# Avionics.net
KiCad netlist of a schematic drawn in Altium Designer
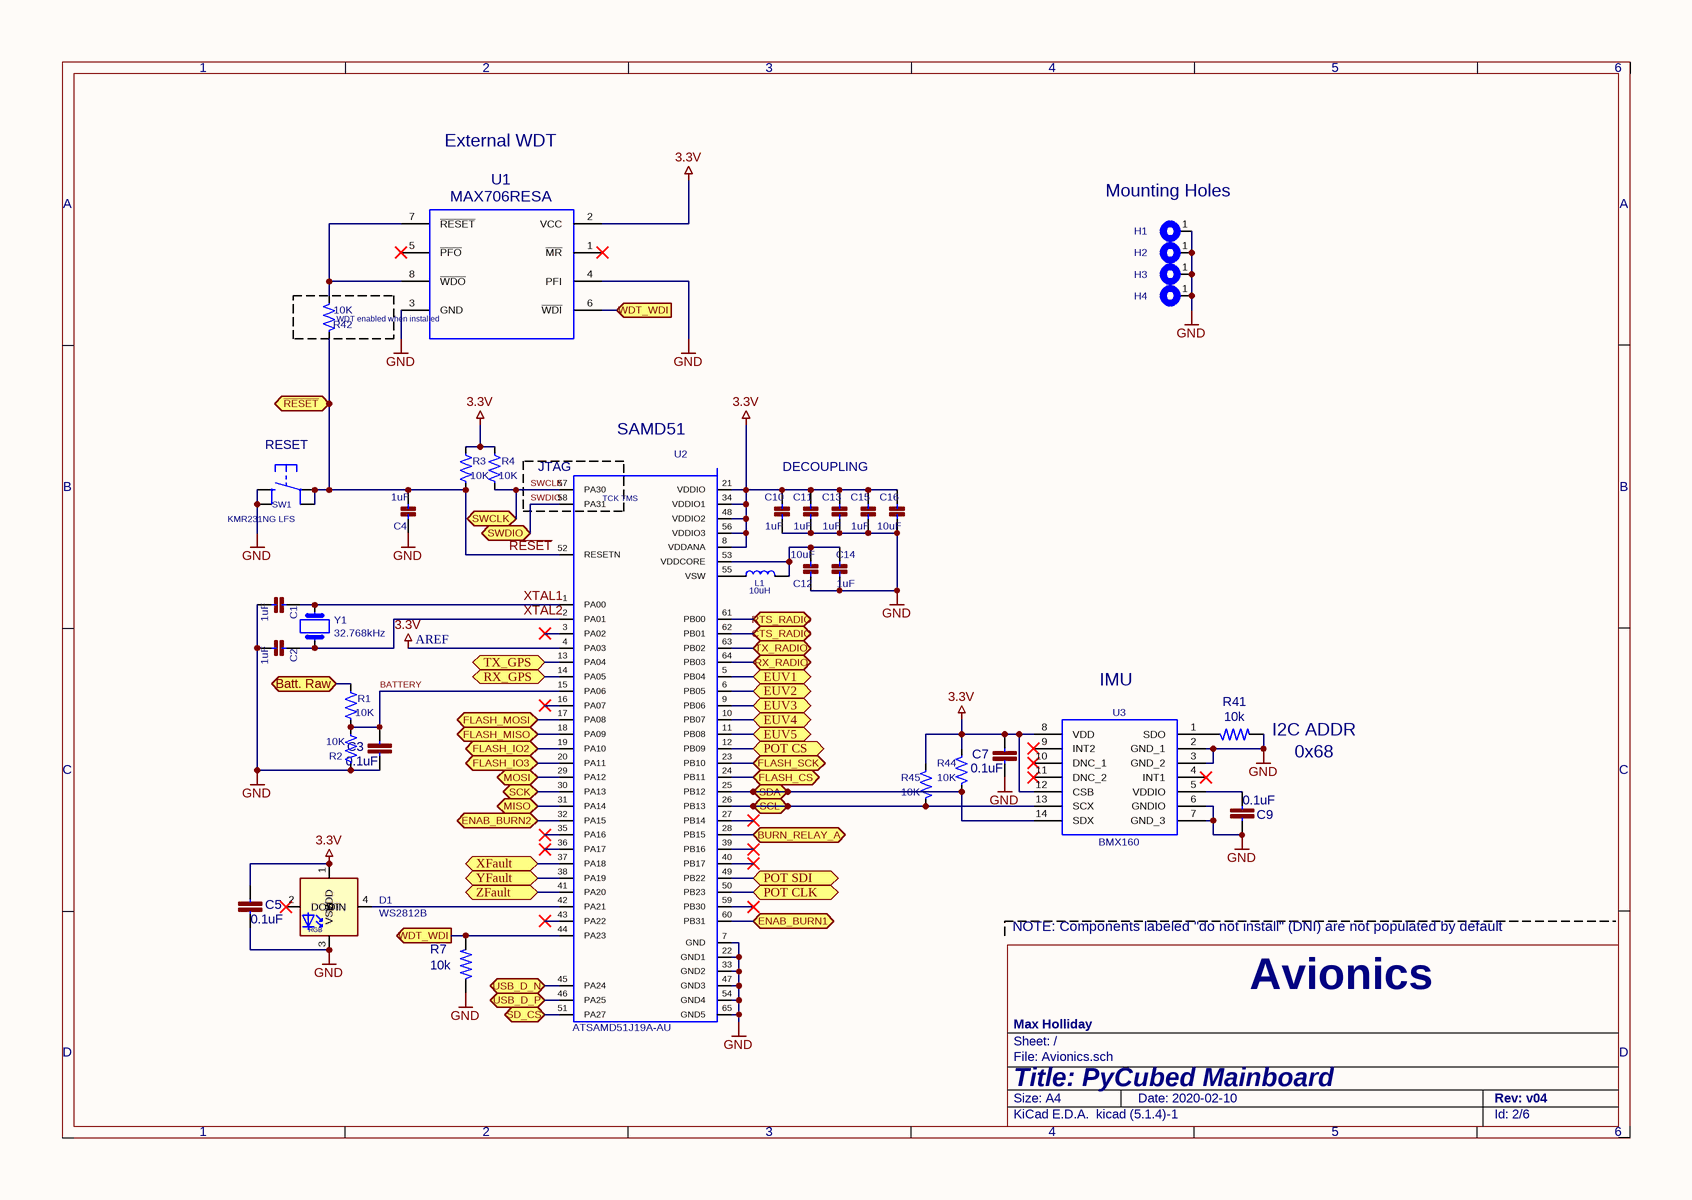
[diagram p0: Avionics.SchDoc]

(export (version "E")
  (design (tool "Eeschema 10.0.6"))
  (components
    (comp (ref "C1")
      (value "1uF")
      (footprint "C_0603_1608Metric")
      (fields (field (name "MPN") "CL10A105KB8NNNC"))
      (libsource (lib "mainboard_1") (part "CAP_CERAMIC0603_NO-Adafruit_Feather_M4_Express-eagle-import-lab64_SAM32-rescue-SAMD-10-rescue-SAM32-rescue"))
    )
    (comp (ref "C2")
      (value "1uF")
      (footprint "C_0603_1608Metric")
      (fields (field (name "MPN") "CL10A105KB8NNNC"))
      (libsource (lib "mainboard_1") (part "CAP_CERAMIC0603_NO-Adafruit_Feather_M4_Express-eagle-import-lab64_SAM32-rescue-SAMD-10-rescue-SAM32-rescue"))
    )
    (comp (ref "C3")
      (value "0.1uF")
      (footprint "C_0603_1608Metric")
      (fields (field (name "MPN") "CL10B104KB8NNNL"))
      (libsource (lib "") (part "0.1UF-25V(+80_-20%)(0603)_2"))
    )
    (comp (ref "C4")
      (value "1uF")
      (footprint "C_0603_1608Metric")
      (fields (field (name "MPN") "CL10A105KB8NNNC"))
      (libsource (lib "") (part "CAP_CERAMIC0603_NO-Adafruit_Feather_M4_Express-eagle-import-lab64_SAM32-rescue-SAMD-10-rescue-SAM32-rescue_1"))
    )
    (comp (ref "C5")
      (value "0.1uF")
      (footprint "C_0603_1608Metric")
      (fields (field (name "MPN") "CL10B104KB8NNNL"))
      (libsource (lib "mainboard_1") (part "0.1UF-25V(+80_-20%)(0603)"))
    )
    (comp (ref "C7")
      (value "0.1uF")
      (footprint "C_0603_1608Metric")
      (fields (field (name "MPN") "CL10B104KB8NNNL"))
      (libsource (lib "") (part "0.1UF-25V(+80_-20%)(0603)_2"))
    )
    (comp (ref "C9")
      (value "0.1uF")
      (footprint "C_0603_1608Metric")
      (fields (field (name "MPN") "CL10B104KB8NNNL"))
      (libsource (lib "") (part "0.1UF-25V(+80_-20%)(0603)_1"))
    )
    (comp (ref "C10")
      (value "1uF")
      (footprint "C_0603_1608Metric")
      (fields (field (name "MPN") "CL10A105KB8NNNC"))
      (libsource (lib "mainboard_1") (part "CAP_CERAMIC0603_NO-Adafruit_Feather_M4_Express-eagle-import-lab64_SAM32-rescue-SAMD-10-rescue-SAM32-rescue"))
    )
    (comp (ref "C11")
      (value "1uF")
      (footprint "C_0603_1608Metric")
      (fields (field (name "MPN") "CL10A105KB8NNNC"))
      (libsource (lib "mainboard_1") (part "CAP_CERAMIC0603_NO-Adafruit_Feather_M4_Express-eagle-import-lab64_SAM32-rescue-SAMD-10-rescue-SAM32-rescue"))
    )
    (comp (ref "C12")
      (value "10uF")
      (footprint "C_0603_1608Metric")
      (fields (field (name "MPN") "CL10A106MP8NNNC"))
      (libsource (lib "") (part "CAP_CERAMIC0805-NOOUTLINE-Adafruit_Feather_M4_Express-eagle-import-lab64_SAM32-rescue-SAMD-10-rescue-SAM32-rescue_1"))
    )
    (comp (ref "C13")
      (value "1uF")
      (footprint "C_0603_1608Metric")
      (fields (field (name "MPN") "CL10A105KB8NNNC"))
      (libsource (lib "mainboard_1") (part "CAP_CERAMIC0603_NO-Adafruit_Feather_M4_Express-eagle-import-lab64_SAM32-rescue-SAMD-10-rescue-SAM32-rescue"))
    )
    (comp (ref "C14")
      (value "1uF")
      (footprint "C_0603_1608Metric")
      (fields (field (name "MPN") "CL10A105KB8NNNC"))
      (libsource (lib "") (part "CAP_CERAMIC0603_NO-Adafruit_Feather_M4_Express-eagle-import-lab64_SAM32-rescue-SAMD-10-rescue-SAM32-rescue_2"))
    )
    (comp (ref "C15")
      (value "1uF")
      (footprint "C_0603_1608Metric")
      (fields (field (name "MPN") "CL10A105KB8NNNC"))
      (libsource (lib "mainboard_1") (part "CAP_CERAMIC0603_NO-Adafruit_Feather_M4_Express-eagle-import-lab64_SAM32-rescue-SAMD-10-rescue-SAM32-rescue"))
    )
    (comp (ref "C16")
      (value "10uF")
      (footprint "C_0603_1608Metric")
      (fields (field (name "MPN") "CL10A106MP8NNNC"))
      (libsource (lib "mainboard_1") (part "CAP_CERAMIC0805-NOOUTLINE-Adafruit_Feather_M4_Express-eagle-import-lab64_SAM32-rescue-SAMD-10-rescue-SAM32-rescue"))
    )
    (comp (ref "D1")
      (value "WS2812B")
      (footprint "LED_WS2812B_PLCC4_5.0x5.0mm_P3.2mm")
      (fields (field (name "MPN") "COM-16347"))
      (libsource (lib "mainboard_1") (part "WS2812B"))
    )
    (comp (ref "H1")
      (value "MountingHole_Pad")
      (footprint "MountingHole_3.2mm_M3_DIN965_Pad")
      (libsource (lib "mainboard_1") (part "MountingHole_Pad"))
    )
    (comp (ref "H2")
      (value "MountingHole_Pad")
      (footprint "MountingHole_3.2mm_M3_DIN965_Pad")
      (libsource (lib "mainboard_1") (part "MountingHole_Pad"))
    )
    (comp (ref "H3")
      (value "MountingHole_Pad")
      (footprint "MountingHole_3.2mm_M3_DIN965_Pad")
      (libsource (lib "mainboard_1") (part "MountingHole_Pad"))
    )
    (comp (ref "H4")
      (value "MountingHole_Pad")
      (footprint "MountingHole_3.2mm_M3_DIN965_Pad")
      (libsource (lib "mainboard_1") (part "MountingHole_Pad"))
    )
    (comp (ref "L1")
      (value "10uH")
      (footprint "L_0805_2012Metric_Pad1.15x1.40mm_HandSolder")
      (fields (field (name "MPN") "LBR2012T100K"))
      (libsource (lib "mainboard_1") (part "INDUCTOR-Adafruit_Feather_M4_Express-eagle-import-lab64_SAM32-rescue-SAMD-10-rescue-SAM32-rescue"))
    )
    (comp (ref "R1")
      (value "10K")
      (footprint "R_0603_1608Metric")
      (fields (field (name "MPN") "CRGCQ0603J10K"))
      (libsource (lib "mainboard_1") (part "R_US"))
    )
    (comp (ref "R2")
      (value "10K")
      (footprint "R_0603_1608Metric")
      (fields (field (name "MPN") "CRGCQ0603J10K"))
      (libsource (lib "mainboard_1") (part "R_US"))
    )
    (comp (ref "R3")
      (value "10K")
      (footprint "R_0603_1608Metric")
      (fields (field (name "MPN") "CRGCQ0603J10K"))
      (libsource (lib "mainboard_1") (part "R_US"))
    )
    (comp (ref "R4")
      (value "10K")
      (footprint "R_0603_1608Metric")
      (fields (field (name "MPN") "CRGCQ0603J10K"))
      (libsource (lib "mainboard_1") (part "R_US"))
    )
    (comp (ref "R7")
      (value "10k")
      (footprint "R_0603_1608Metric")
      (fields (field (name "MPN") "RNCP0603FTD10K0"))
      (libsource (lib "mainboard_1") (part "R-US_R0603"))
    )
    (comp (ref "R41")
      (value "10k")
      (footprint "R_0603_1608Metric")
      (fields (field (name "MPN") "RNCP0603FTD10K0"))
      (libsource (lib "mainboard_1") (part "R-US_R0603"))
    )
    (comp (ref "R42")
      (value "10K")
      (footprint "R_0603_1608Metric")
      (fields (field (name "MPN") "CRGCQ0603J10K"))
      (libsource (lib "mainboard_1") (part "R_US"))
    )
    (comp (ref "R44")
      (value "10K")
      (footprint "R_0603_1608Metric")
      (fields (field (name "MPN") "CRGCQ0603J10K"))
      (libsource (lib "mainboard_1") (part "R_US"))
    )
    (comp (ref "R45")
      (value "10K")
      (footprint "R_0603_1608Metric")
      (fields (field (name "MPN") "CRGCQ0603J10K"))
      (libsource (lib "mainboard_1") (part "R_US"))
    )
    (comp (ref "SW1")
      (value "KMR231NG LFS")
      (footprint "BTN_KMR2_4.6X2.8")
      (libsource (lib "mainboard_1") (part "SWITCH_TACT_SMT4.6X2.8-Adafruit_Feather_M4_Express-eagle-import-lab64_SAM32-rescue-SAMD-10-rescue-SAM32-rescue"))
    )
    (comp (ref "U1")
      (value "MAX706RESA")
      (footprint "SO-8_3.9x4.9mm_P1.27mm")
      (libsource (lib "mainboard_1") (part "MAX708RESA-T"))
    )
    (comp (ref "U2")
      (value "120MHZ 512KB Flash 64 TQFP")
      (footprint "ATSAMD51J19A-MU")
      (fields (field (name "PROTO") "ATSAMD51J19A-AU") (field (name "MPN") "ATSAMD51J19A-AU"))
      (libsource (lib "mainboard_1") (part "ATSAMD51J20A-AU-ATSAMD51J20A-AU-lab64_SAM32-rescue-lab64_SAM32-rescue-SAMD-10-rescue-SAM32-rescue"))
    )
    (comp (ref "U3") (value "BMX160") (footprint "BMX160") (libsource (lib "mainboard_1") (part "BMX160")))
    (comp (ref "Y1")
      (value "32.768kHz")
      (footprint "Crystal_SMD_3215-2Pin_3.2x1.5mm")
      (fields (field (name "MPN") "ABS07-32.768KHZ-T"))
      (libsource (lib "mainboard_1") (part "Crystal"))
    )
  )
  (nets
    (net (code "1") (name "/BATTERY") (class "Default")
      (node (ref "C3") (pin "1") (pinfunction "1_1") (pintype "passive"))
      (node (ref "R1") (pin "2") (pinfunction "2_2") (pintype "passive"))
      (node (ref "R2") (pin "2") (pinfunction "2_2") (pintype "passive"))
      (node (ref "U2") (pin "15") (pinfunction "PA06_15") (pintype "passive"))
    )
    (net (code "2") (name "/BURN_RELAY_A") (class "Default")
      (node (ref "U2") (pin "28") (pinfunction "PB15_28") (pintype "passive"))
    )
    (net (code "3") (name "/Batt. Raw") (class "Default")
      (node (ref "R1") (pin "1") (pinfunction "1_1") (pintype "passive"))
    )
    (net (code "4") (name "/CTS_RADIO") (class "Default")
      (node (ref "U2") (pin "62") (pinfunction "PB01_62") (pintype "passive"))
    )
    (net (code "5") (name "/ENAB_BURN1") (class "Default")
      (node (ref "U2") (pin "60") (pinfunction "PB31_60") (pintype "passive"))
    )
    (net (code "6") (name "/ENAB_BURN2") (class "Default")
      (node (ref "U2") (pin "32") (pinfunction "PA15_32") (pintype "passive"))
    )
    (net (code "7") (name "/EUV1") (class "Default")
      (node (ref "U2") (pin "5") (pinfunction "PB04_5") (pintype "passive"))
    )
    (net (code "8") (name "/EUV2") (class "Default")
      (node (ref "U2") (pin "6") (pinfunction "PB05_6") (pintype "passive"))
    )
    (net (code "9") (name "/EUV3") (class "Default")
      (node (ref "U2") (pin "9") (pinfunction "PB06_9") (pintype "passive"))
    )
    (net (code "10") (name "/EUV4") (class "Default")
      (node (ref "U2") (pin "10") (pinfunction "PB07_10") (pintype "passive"))
    )
    (net (code "11") (name "/EUV5") (class "Default")
      (node (ref "U2") (pin "11") (pinfunction "PB08_11") (pintype "passive"))
    )
    (net (code "12") (name "/FLASH_CS") (class "Default")
      (node (ref "U2") (pin "24") (pinfunction "PB11_24") (pintype "passive"))
    )
    (net (code "13") (name "/FLASH_IO2") (class "Default")
      (node (ref "U2") (pin "19") (pinfunction "PA10_19") (pintype "passive"))
    )
    (net (code "14") (name "/FLASH_IO3") (class "Default")
      (node (ref "U2") (pin "20") (pinfunction "PA11_20") (pintype "passive"))
    )
    (net (code "15") (name "/FLASH_MISO") (class "Default")
      (node (ref "U2") (pin "18") (pinfunction "PA09_18") (pintype "passive"))
    )
    (net (code "16") (name "/FLASH_MOSI") (class "Default")
      (node (ref "U2") (pin "17") (pinfunction "PA08_17") (pintype "passive"))
    )
    (net (code "17") (name "/FLASH_SCK") (class "Default")
      (node (ref "U2") (pin "23") (pinfunction "PB10_23") (pintype "passive"))
    )
    (net (code "18") (name "/MISO") (class "Default")
      (node (ref "U2") (pin "31") (pinfunction "PA14_31") (pintype "passive"))
    )
    (net (code "19") (name "/MOSI") (class "Default")
      (node (ref "U2") (pin "29") (pinfunction "PA12_29") (pintype "passive"))
    )
    (net (code "20") (name "/POT CLK") (class "Default")
      (node (ref "U2") (pin "50") (pinfunction "PB23_50") (pintype "passive"))
    )
    (net (code "21") (name "/POT CS") (class "Default")
      (node (ref "U2") (pin "12") (pinfunction "PB09_12") (pintype "passive"))
    )
    (net (code "22") (name "/POT SDI") (class "Default")
      (node (ref "U2") (pin "49") (pinfunction "PB22_49") (pintype "passive"))
    )
    (net (code "23") (name "/RTS_RADIO") (class "Default")
      (node (ref "U2") (pin "61") (pinfunction "PB00_61") (pintype "passive"))
    )
    (net (code "24") (name "/RX_GPS") (class "Default")
      (node (ref "U2") (pin "14") (pinfunction "PA05_14") (pintype "passive"))
    )
    (net (code "25") (name "/RX_RADIO") (class "Default")
      (node (ref "U2") (pin "64") (pinfunction "PB03_64") (pintype "passive"))
    )
    (net (code "26") (name "/SCK") (class "Default")
      (node (ref "U2") (pin "30") (pinfunction "PA13_30") (pintype "passive"))
    )
    (net (code "27") (name "/SCL") (class "Default")
      (node (ref "R45") (pin "2") (pinfunction "2_2") (pintype "passive"))
      (node (ref "U2") (pin "26") (pinfunction "PB13_26") (pintype "passive"))
      (node (ref "U3") (pin "13") (pinfunction "SCX_13") (pintype "passive"))
    )
    (net (code "28") (name "/SDA") (class "Default")
      (node (ref "R44") (pin "2") (pinfunction "2_2") (pintype "passive"))
      (node (ref "U2") (pin "25") (pinfunction "PB12_25") (pintype "passive"))
      (node (ref "U3") (pin "14") (pinfunction "SDX_14") (pintype "passive"))
    )
    (net (code "29") (name "/SD_CS") (class "Default")
      (node (ref "U2") (pin "51") (pinfunction "PA27_51") (pintype "passive"))
    )
    (net (code "30") (name "/SWCLK") (class "Default")
      (node (ref "R4") (pin "2") (pinfunction "2_2") (pintype "passive"))
      (node (ref "U2") (pin "57") (pinfunction "PA30_57") (pintype "passive"))
    )
    (net (code "31") (name "/SWDIO") (class "Default")
      (node (ref "U2") (pin "58") (pinfunction "PA31_58") (pintype "passive"))
    )
    (net (code "32") (name "/TX_GPS") (class "Default")
      (node (ref "U2") (pin "13") (pinfunction "PA04_13") (pintype "passive"))
    )
    (net (code "33") (name "/TX_RADIO") (class "Default")
      (node (ref "U2") (pin "63") (pinfunction "PB02_63") (pintype "passive"))
    )
    (net (code "34") (name "/USB_D_N") (class "Default")
      (node (ref "U2") (pin "45") (pinfunction "PA24_45") (pintype "passive"))
    )
    (net (code "35") (name "/USB_D_P") (class "Default")
      (node (ref "U2") (pin "46") (pinfunction "PA25_46") (pintype "passive"))
    )
    (net (code "36") (name "/WDT_WDI") (class "Default")
      (node (ref "R7") (pin "2") (pinfunction "2_2") (pintype "passive"))
      (node (ref "U1") (pin "6") (pinfunction "~{WDI}_6") (pintype "passive"))
      (node (ref "U2") (pin "44") (pinfunction "PA23_44") (pintype "passive"))
    )
    (net (code "37") (name "/XFault") (class "Default")
      (node (ref "U2") (pin "37") (pinfunction "PA18_37") (pintype "passive"))
    )
    (net (code "38") (name "/XTAL1") (class "Default")
      (node (ref "C1") (pin "1") (pinfunction "1_1") (pintype "passive"))
      (node (ref "U2") (pin "1") (pinfunction "PA00_1") (pintype "passive"))
      (node (ref "Y1") (pin "1") (pinfunction "1_1") (pintype "passive"))
    )
    (net (code "39") (name "/XTAL2") (class "Default")
      (node (ref "C2") (pin "1") (pinfunction "1_1") (pintype "passive"))
      (node (ref "U2") (pin "2") (pinfunction "PA01_2") (pintype "passive"))
      (node (ref "Y1") (pin "2") (pinfunction "2_2") (pintype "passive"))
    )
    (net (code "40") (name "/YFault") (class "Default")
      (node (ref "U2") (pin "38") (pinfunction "PA19_38") (pintype "passive"))
    )
    (net (code "41") (name "/ZFault") (class "Default")
      (node (ref "U2") (pin "41") (pinfunction "PA20_41") (pintype "passive"))
    )
    (net (code "42") (name "/~{RESET}") (class "Default")
      (node (ref "C4") (pin "2") (pinfunction "2_2") (pintype "passive"))
      (node (ref "R3") (pin "2") (pinfunction "2_2") (pintype "passive"))
      (node (ref "R42") (pin "1") (pinfunction "1_1") (pintype "passive"))
      (node (ref "SW1") (pin "A") (pinfunction "P_A") (pintype "passive"))
      (node (ref "SW1") (pin "A'") (pinfunction "P1_A'") (pintype "passive"))
      (node (ref "U2") (pin "52") (pinfunction "RESETN_52") (pintype "passive"))
    )
    (net (code "43") (name "3.3V") (class "Default")
      (node (ref "C10") (pin "1") (pinfunction "1_1") (pintype "passive"))
      (node (ref "C11") (pin "1") (pinfunction "1_1") (pintype "passive"))
      (node (ref "C13") (pin "1") (pinfunction "1_1") (pintype "passive"))
      (node (ref "C15") (pin "1") (pinfunction "1_1") (pintype "passive"))
      (node (ref "C16") (pin "1") (pinfunction "1_1") (pintype "passive"))
      (node (ref "C5") (pin "1") (pinfunction "1_1") (pintype "passive"))
      (node (ref "C7") (pin "1") (pinfunction "1_1") (pintype "passive"))
      (node (ref "D1") (pin "1") (pinfunction "VDD_1") (pintype "passive"))
      (node (ref "R3") (pin "1") (pinfunction "1_1") (pintype "passive"))
      (node (ref "R4") (pin "1") (pinfunction "1_1") (pintype "passive"))
      (node (ref "R44") (pin "1") (pinfunction "1_1") (pintype "passive"))
      (node (ref "R45") (pin "1") (pinfunction "1_1") (pintype "passive"))
      (node (ref "U1") (pin "2") (pinfunction "VCC_2") (pintype "passive"))
      (node (ref "U2") (pin "21") (pinfunction "VDDIO_21") (pintype "passive"))
      (node (ref "U2") (pin "34") (pinfunction "VDDIO1_34") (pintype "passive"))
      (node (ref "U2") (pin "4") (pinfunction "PA03_4") (pintype "passive"))
      (node (ref "U2") (pin "48") (pinfunction "VDDIO2_48") (pintype "passive"))
      (node (ref "U2") (pin "56") (pinfunction "VDDIO3_56") (pintype "passive"))
      (node (ref "U2") (pin "8") (pinfunction "VDDANA_8") (pintype "passive"))
      (node (ref "U3") (pin "12") (pinfunction "CSB_12") (pintype "passive"))
      (node (ref "U3") (pin "8") (pinfunction "VDD_8") (pintype "passive"))
    )
    (net (code "44") (name "GND") (class "Default")
      (node (ref "C1") (pin "2") (pinfunction "2_2") (pintype "passive"))
      (node (ref "C10") (pin "2") (pinfunction "2_2") (pintype "passive"))
      (node (ref "C11") (pin "2") (pinfunction "2_2") (pintype "passive"))
      (node (ref "C12") (pin "1") (pinfunction "1_1") (pintype "passive"))
      (node (ref "C13") (pin "2") (pinfunction "2_2") (pintype "passive"))
      (node (ref "C14") (pin "2") (pinfunction "2_2") (pintype "passive"))
      (node (ref "C15") (pin "2") (pinfunction "2_2") (pintype "passive"))
      (node (ref "C16") (pin "2") (pinfunction "2_2") (pintype "passive"))
      (node (ref "C2") (pin "2") (pinfunction "2_2") (pintype "passive"))
      (node (ref "C3") (pin "2") (pinfunction "2_2") (pintype "passive"))
      (node (ref "C4") (pin "1") (pinfunction "1_1") (pintype "passive"))
      (node (ref "C5") (pin "2") (pinfunction "2_2") (pintype "passive"))
      (node (ref "C7") (pin "2") (pinfunction "2_2") (pintype "passive"))
      (node (ref "C9") (pin "1") (pinfunction "1_1") (pintype "passive"))
      (node (ref "D1") (pin "3") (pinfunction "VSS_3") (pintype "passive"))
      (node (ref "H1") (pin "1") (pinfunction "1_1") (pintype "passive"))
      (node (ref "H2") (pin "1") (pinfunction "1_1") (pintype "passive"))
      (node (ref "H3") (pin "1") (pinfunction "1_1") (pintype "passive"))
      (node (ref "H4") (pin "1") (pinfunction "1_1") (pintype "passive"))
      (node (ref "R2") (pin "1") (pinfunction "1_1") (pintype "passive"))
      (node (ref "R41") (pin "2") (pinfunction "2_2") (pintype "passive"))
      (node (ref "R7") (pin "1") (pinfunction "1_1") (pintype "passive"))
      (node (ref "SW1") (pin "B") (pinfunction "S_B") (pintype "passive"))
      (node (ref "SW1") (pin "B'") (pinfunction "S1_B'") (pintype "passive"))
      (node (ref "U1") (pin "3") (pinfunction "GND_3") (pintype "passive"))
      (node (ref "U1") (pin "4") (pinfunction "PFI_4") (pintype "passive"))
      (node (ref "U2") (pin "22") (pinfunction "GND1_22") (pintype "passive"))
      (node (ref "U2") (pin "33") (pinfunction "GND2_33") (pintype "passive"))
      (node (ref "U2") (pin "47") (pinfunction "GND3_47") (pintype "passive"))
      (node (ref "U2") (pin "54") (pinfunction "GND4_54") (pintype "passive"))
      (node (ref "U2") (pin "65") (pinfunction "GND5_65") (pintype "passive"))
      (node (ref "U2") (pin "7") (pinfunction "GND_7") (pintype "passive"))
      (node (ref "U3") (pin "2") (pinfunction "GND_1_2") (pintype "passive"))
      (node (ref "U3") (pin "3") (pinfunction "GND_2_3") (pintype "passive"))
      (node (ref "U3") (pin "6") (pinfunction "GNDIO_6") (pintype "passive"))
      (node (ref "U3") (pin "7") (pinfunction "GND_3_7") (pintype "passive"))
    )
    (net (code "45") (name "Net-(D1-DIN)") (class "Default")
      (node (ref "D1") (pin "4") (pinfunction "DIN_4") (pintype "passive"))
      (node (ref "U2") (pin "42") (pinfunction "PA21_42") (pintype "passive"))
    )
    (net (code "46") (name "Net-(U1-~{RESET})") (class "Default")
      (node (ref "R42") (pin "2") (pinfunction "2_2") (pintype "passive"))
      (node (ref "U1") (pin "7") (pinfunction "~{RESET}_7") (pintype "passive"))
      (node (ref "U1") (pin "8") (pinfunction "~{WDO}_8") (pintype "passive"))
    )
    (net (code "47") (name "Net-(U2-VDDCORE)") (class "Default")
      (node (ref "C12") (pin "2") (pinfunction "2_2") (pintype "passive"))
      (node (ref "C14") (pin "1") (pinfunction "1_1") (pintype "passive"))
      (node (ref "L1") (pin "1") (pinfunction "1_1") (pintype "passive"))
      (node (ref "U2") (pin "53") (pinfunction "VDDCORE_53") (pintype "passive"))
    )
    (net (code "48") (name "Net-(U2-VSW)") (class "Default")
      (node (ref "L1") (pin "2") (pinfunction "2_2") (pintype "passive"))
      (node (ref "U2") (pin "55") (pinfunction "VSW_55") (pintype "passive"))
    )
    (net (code "49") (name "Net-(U3-SDO)") (class "Default")
      (node (ref "R41") (pin "1") (pinfunction "1_1") (pintype "passive"))
      (node (ref "U3") (pin "1") (pinfunction "SDO_1") (pintype "passive"))
    )
    (net (code "50") (name "Net-(U3-VDDIO)") (class "Default")
      (node (ref "C9") (pin "2") (pinfunction "2_2") (pintype "passive"))
      (node (ref "U3") (pin "5") (pinfunction "VDDIO_5") (pintype "passive"))
    )
    (net (code "51") (name "unconnected-(D1-DOUT-Pad2)") (class "Default")
      (node (ref "D1") (pin "2") (pinfunction "DOUT_2") (pintype "passive+no_connect"))
    )
    (net (code "52") (name "unconnected-(U1-~{MR}-Pad1)") (class "Default")
      (node (ref "U1") (pin "1") (pinfunction "~{MR}_1") (pintype "passive+no_connect"))
    )
    (net (code "53") (name "unconnected-(U1-~{PFO}-Pad5)") (class "Default")
      (node (ref "U1") (pin "5") (pinfunction "~{PFO}_5") (pintype "passive+no_connect"))
    )
    (net (code "54") (name "unconnected-(U2-PA02-Pad3)") (class "Default")
      (node (ref "U2") (pin "3") (pinfunction "PA02_3") (pintype "passive+no_connect"))
    )
    (net (code "55") (name "unconnected-(U2-PA07-Pad16)") (class "Default")
      (node (ref "U2") (pin "16") (pinfunction "PA07_16") (pintype "passive+no_connect"))
    )
    (net (code "56") (name "unconnected-(U2-PA16-Pad35)") (class "Default")
      (node (ref "U2") (pin "35") (pinfunction "PA16_35") (pintype "passive+no_connect"))
    )
    (net (code "57") (name "unconnected-(U2-PA17-Pad36)") (class "Default")
      (node (ref "U2") (pin "36") (pinfunction "PA17_36") (pintype "passive+no_connect"))
    )
    (net (code "58") (name "unconnected-(U2-PA22-Pad43)") (class "Default")
      (node (ref "U2") (pin "43") (pinfunction "PA22_43") (pintype "passive+no_connect"))
    )
    (net (code "59") (name "unconnected-(U2-PB14-Pad27)") (class "Default")
      (node (ref "U2") (pin "27") (pinfunction "PB14_27") (pintype "passive+no_connect"))
    )
    (net (code "60") (name "unconnected-(U2-PB16-Pad39)") (class "Default")
      (node (ref "U2") (pin "39") (pinfunction "PB16_39") (pintype "passive+no_connect"))
    )
    (net (code "61") (name "unconnected-(U2-PB17-Pad40)") (class "Default")
      (node (ref "U2") (pin "40") (pinfunction "PB17_40") (pintype "passive+no_connect"))
    )
    (net (code "62") (name "unconnected-(U2-PB30-Pad59)") (class "Default")
      (node (ref "U2") (pin "59") (pinfunction "PB30_59") (pintype "passive+no_connect"))
    )
    (net (code "63") (name "unconnected-(U3-DNC_1-Pad10)") (class "Default")
      (node (ref "U3") (pin "10") (pinfunction "DNC_1_10") (pintype "passive+no_connect"))
    )
    (net (code "64") (name "unconnected-(U3-DNC_2-Pad11)") (class "Default")
      (node (ref "U3") (pin "11") (pinfunction "DNC_2_11") (pintype "passive+no_connect"))
    )
    (net (code "65") (name "unconnected-(U3-INT1-Pad4)") (class "Default")
      (node (ref "U3") (pin "4") (pinfunction "INT1_4") (pintype "passive+no_connect"))
    )
    (net (code "66") (name "unconnected-(U3-INT2-Pad9)") (class "Default")
      (node (ref "U3") (pin "9") (pinfunction "INT2_9") (pintype "passive+no_connect"))
    )
  )
)
